# schematics.net
KiCad netlist of a schematic drawn in EasyEDA
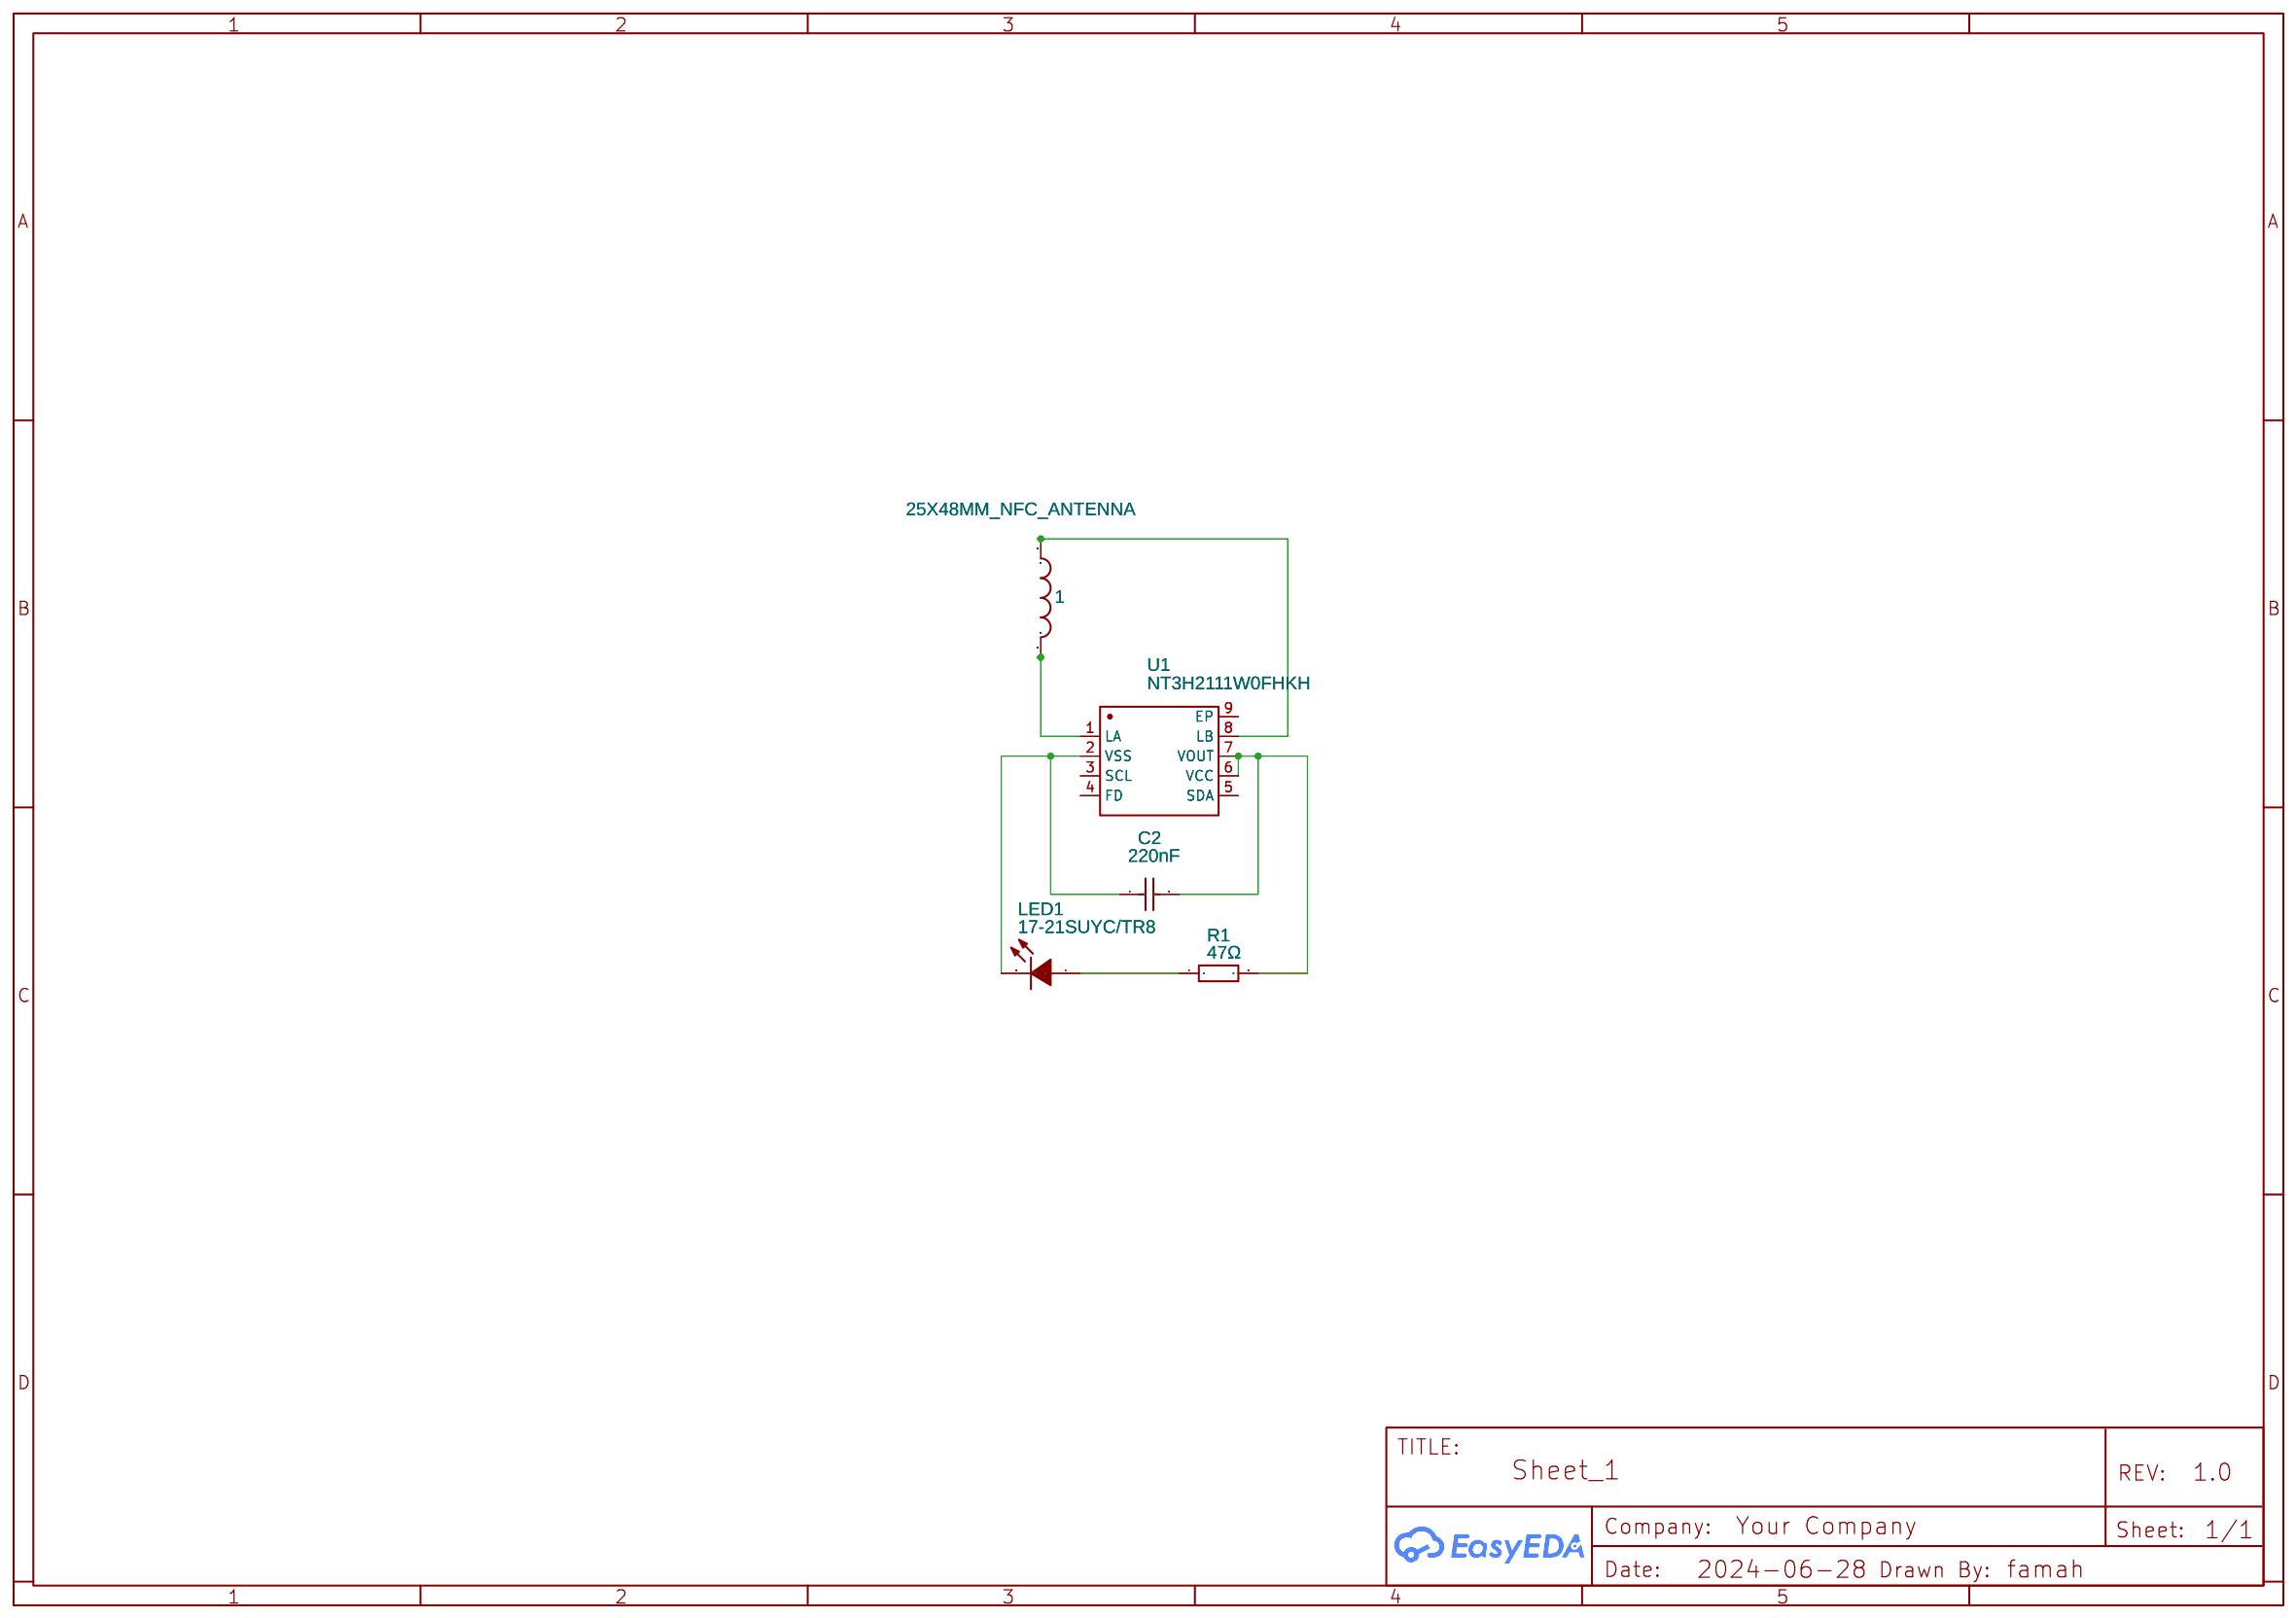
[diagram p0: schematic sheet]

(export (version "E")
  (design (tool "Eeschema 10.0.6"))
  (components
    (comp (ref "1") (value "25X48MM_NFC_ANTENNA") (libsource (lib "") (part "25X48MM_NFC_ANTENNA")))
    (comp (ref "C2")
      (value "220nF")
      (fields
        (field (name "Manufacturer Part") "CL10B224KA8NNNC")
        (field (name "Manufacturer") "SAMSUNG(三星)")
      )
      (libsource (lib "") (part "CL10B224KA8NNNC"))
    )
    (comp (ref "LED1")
      (value "17-21SUYC/TR8")
      (fields (field (name "Manufacturer Part") "KT-0805黄灯") (field (name "Manufacturer") "KENTO"))
      (libsource (lib "") (part "17-21SUYC/TR8"))
    )
    (comp (ref "R1")
      (value "47Ω")
      (fields
        (field (name "Manufacturer Part") "0603WAF470JT5E")
        (field (name "Manufacturer") "UNI-ROYAL(厚声)")
      )
      (libsource (lib "") (part "0603WAF470JT5E"))
    )
    (comp (ref "U1")
      (value "NT3H2111W0FHKH")
      (fields (field (name "Manufacturer") "NXP(恩智浦)"))
      (libsource (lib "") (part "NT3H2111W0FHKH"))
    )
  )
  (nets
    (net (code "1") (name "Net-(LED1-+)") (class "Default")
      (node (ref "LED1") (pin "1") (pinfunction "+_1") (pintype "unspecified"))
      (node (ref "R1") (pin "1") (pinfunction "1_1") (pintype "input"))
    )
    (net (code "2") (name "Net-(LED1--)") (class "Default")
      (node (ref "C2") (pin "1") (pinfunction "1_1") (pintype "input"))
      (node (ref "LED1") (pin "2") (pinfunction "-_2") (pintype "unspecified"))
      (node (ref "U1") (pin "2") (pinfunction "VSS_2") (pintype "unspecified"))
    )
    (net (code "3") (name "Net-(U1-LA)") (class "Default")
      (node (ref "1") (pin "P$2") (pinfunction "P$2_P$2") (pintype "bidirectional"))
      (node (ref "U1") (pin "1") (pinfunction "LA_1") (pintype "unspecified"))
    )
    (net (code "4") (name "Net-(U1-LB)") (class "Default")
      (node (ref "1") (pin "P$1") (pinfunction "P$1_P$1") (pintype "bidirectional"))
      (node (ref "U1") (pin "8") (pinfunction "LB_8") (pintype "unspecified"))
    )
    (net (code "5") (name "Net-(U1-VCC)") (class "Default")
      (node (ref "C2") (pin "2") (pinfunction "2_2") (pintype "input"))
      (node (ref "R1") (pin "2") (pinfunction "2_2") (pintype "input"))
      (node (ref "U1") (pin "6") (pinfunction "VCC_6") (pintype "unspecified"))
      (node (ref "U1") (pin "7") (pinfunction "VOUT_7") (pintype "unspecified"))
    )
    (net (code "6") (name "unconnected-(U1-EP-Pad9)") (class "Default")
      (node (ref "U1") (pin "9") (pinfunction "EP_9") (pintype "unspecified"))
    )
    (net (code "7") (name "unconnected-(U1-FD-Pad4)") (class "Default")
      (node (ref "U1") (pin "4") (pinfunction "FD_4") (pintype "unspecified"))
    )
    (net (code "8") (name "unconnected-(U1-SCL-Pad3)") (class "Default")
      (node (ref "U1") (pin "3") (pinfunction "SCL_3") (pintype "unspecified"))
    )
    (net (code "9") (name "unconnected-(U1-SDA-Pad5)") (class "Default")
      (node (ref "U1") (pin "5") (pinfunction "SDA_5") (pintype "unspecified"))
    )
  )
)
